# SHARED_HEADER.net
KiCad netlist of a schematic drawn in Altium Designer
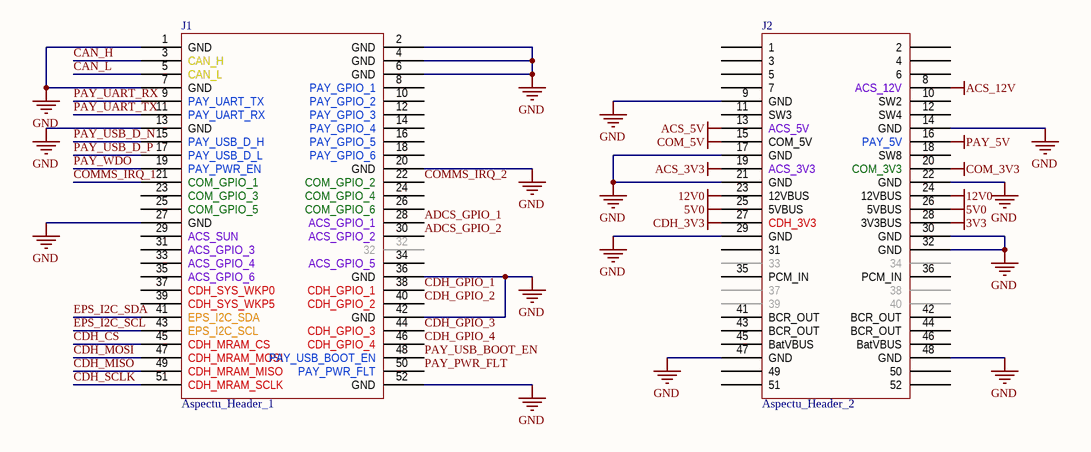
[diagram p0: SHARED_HEADER.SchDoc]

(export (version "E")
  (design (tool "Eeschema 10.0.6"))
  (components
    (comp (ref "J1")
      (value "Aspectu_Header_1")
      (footprint "Aspectu_Header_1")
      (description "Aspectu Header 1")
      (libsource (lib "UBC_Orbit_Shared_Components") (part "Aspectu_Header_1"))
    )
    (comp (ref "J2")
      (value "Aspectu_Header_2")
      (footprint "Aspectu_Header_2")
      (description "Aspectu Header 2")
      (libsource (lib "UBC_Orbit_Shared_Components") (part "Aspectu_Header_2"))
    )
  )
  (nets
    (net (code "1") (name "/ADCS_GPIO_1") (class "Default")
      (node (ref "J1") (pin "28") (pinfunction "ACS_GPIO_1_28") (pintype "passive"))
    )
    (net (code "2") (name "/ADCS_GPIO_2") (class "Default")
      (node (ref "J1") (pin "30") (pinfunction "ACS_GPIO_2_30") (pintype "passive"))
    )
    (net (code "3") (name "/CAN_H") (class "Default")
      (node (ref "J1") (pin "3") (pinfunction "CAN_H_3") (pintype "passive"))
    )
    (net (code "4") (name "/CAN_L") (class "Default")
      (node (ref "J1") (pin "5") (pinfunction "CAN_L_5") (pintype "passive"))
    )
    (net (code "5") (name "/CDH_CS") (class "Default")
      (node (ref "J1") (pin "45") (pinfunction "CDH_MRAM_CS_45") (pintype "passive"))
    )
    (net (code "6") (name "/CDH_GPIO_1") (class "Default")
      (node (ref "J1") (pin "38") (pinfunction "CDH_GPIO_1_38") (pintype "passive"))
    )
    (net (code "7") (name "/CDH_GPIO_2") (class "Default")
      (node (ref "J1") (pin "40") (pinfunction "CDH_GPIO_2_40") (pintype "passive"))
    )
    (net (code "8") (name "/CDH_GPIO_3") (class "Default")
      (node (ref "J1") (pin "44") (pinfunction "CDH_GPIO_3_44") (pintype "passive"))
    )
    (net (code "9") (name "/CDH_GPIO_4") (class "Default")
      (node (ref "J1") (pin "46") (pinfunction "CDH_GPIO_4_46") (pintype "passive"))
    )
    (net (code "10") (name "/CDH_MISO") (class "Default")
      (node (ref "J1") (pin "49") (pinfunction "CDH_MRAM_MISO_49") (pintype "passive"))
    )
    (net (code "11") (name "/CDH_MOSI") (class "Default")
      (node (ref "J1") (pin "47") (pinfunction "CDH_MRAM_MOSI_47") (pintype "passive"))
    )
    (net (code "12") (name "/CDH_SCLK") (class "Default")
      (node (ref "J1") (pin "51") (pinfunction "CDH_MRAM_SCLK_51") (pintype "passive"))
    )
    (net (code "13") (name "/COMMS_IRQ_1") (class "Default")
      (node (ref "J1") (pin "21") (pinfunction "COM_GPIO_1_21") (pintype "passive"))
    )
    (net (code "14") (name "/COMMS_IRQ_2") (class "Default")
      (node (ref "J1") (pin "22") (pinfunction "COM_GPIO_2_22") (pintype "passive"))
    )
    (net (code "15") (name "/EPS_I2C_SCL") (class "Default")
      (node (ref "J1") (pin "43") (pinfunction "EPS_I2C_SCL_43") (pintype "passive"))
    )
    (net (code "16") (name "/EPS_I2C_SDA") (class "Default")
      (node (ref "J1") (pin "41") (pinfunction "EPS_I2C_SDA_41") (pintype "passive"))
    )
    (net (code "17") (name "/PAY_PWR_FLT") (class "Default")
      (node (ref "J1") (pin "50") (pinfunction "PAY_PWR_FLT_50") (pintype "passive"))
    )
    (net (code "18") (name "/PAY_UART_RX") (class "Default")
      (node (ref "J1") (pin "9") (pinfunction "PAY_UART_TX_9") (pintype "passive"))
    )
    (net (code "19") (name "/PAY_UART_TX") (class "Default")
      (node (ref "J1") (pin "11") (pinfunction "PAY_UART_RX_11") (pintype "passive"))
    )
    (net (code "20") (name "/PAY_USB_BOOT_EN") (class "Default")
      (node (ref "J1") (pin "48") (pinfunction "PAY_USB_BOOT_EN_48") (pintype "passive"))
    )
    (net (code "21") (name "/PAY_USB_D_N") (class "Default")
      (node (ref "J1") (pin "15") (pinfunction "PAY_USB_D_H_15") (pintype "passive"))
    )
    (net (code "22") (name "/PAY_USB_D_P") (class "Default")
      (node (ref "J1") (pin "17") (pinfunction "PAY_USB_D_L_17") (pintype "passive"))
    )
    (net (code "23") (name "/PAY_WDO") (class "Default")
      (node (ref "J1") (pin "19") (pinfunction "PAY_PWR_EN_19") (pintype "passive"))
    )
    (net (code "24") (name "3V3") (class "Default")
      (node (ref "J2") (pin "28") (pinfunction "3V3BUS_28") (pintype "power_in"))
    )
    (net (code "25") (name "5V0") (class "Default")
      (node (ref "J2") (pin "25") (pinfunction "5VBUS_25") (pintype "power_in"))
      (node (ref "J2") (pin "26") (pinfunction "5VBUS_26") (pintype "power_in"))
    )
    (net (code "26") (name "12V0") (class "Default")
      (node (ref "J2") (pin "23") (pinfunction "12VBUS_23") (pintype "power_in"))
      (node (ref "J2") (pin "24") (pinfunction "12VBUS_24") (pintype "power_in"))
    )
    (net (code "27") (name "ACS_3V3") (class "Default")
      (node (ref "J2") (pin "19") (pinfunction "ACS_3V3_19") (pintype "passive"))
    )
    (net (code "28") (name "ACS_5V") (class "Default")
      (node (ref "J2") (pin "13") (pinfunction "ACS_5V_13") (pintype "passive"))
    )
    (net (code "29") (name "ACS_12V") (class "Default")
      (node (ref "J2") (pin "8") (pinfunction "ACS_12V_8") (pintype "passive"))
    )
    (net (code "30") (name "CDH_3V3") (class "Default")
      (node (ref "J2") (pin "27") (pinfunction "CDH_3V3_27") (pintype "power_in"))
    )
    (net (code "31") (name "COM_3V3") (class "Default")
      (node (ref "J2") (pin "20") (pinfunction "COM_3V3_20") (pintype "passive"))
    )
    (net (code "32") (name "COM_5V") (class "Default")
      (node (ref "J2") (pin "15") (pinfunction "COM_5V_15") (pintype "passive"))
    )
    (net (code "33") (name "GND") (class "Default")
      (node (ref "J1") (pin "1") (pinfunction "GND_1") (pintype "power_in"))
      (node (ref "J1") (pin "13") (pinfunction "GND_13") (pintype "passive"))
      (node (ref "J1") (pin "2") (pinfunction "GND_2") (pintype "power_in"))
      (node (ref "J1") (pin "20") (pinfunction "GND_20") (pintype "power_in"))
      (node (ref "J1") (pin "27") (pinfunction "GND_27") (pintype "power_in"))
      (node (ref "J1") (pin "36") (pinfunction "GND_36") (pintype "power_in"))
      (node (ref "J1") (pin "4") (pinfunction "GND_4") (pintype "power_in"))
      (node (ref "J1") (pin "42") (pinfunction "GND_42") (pintype "power_in"))
      (node (ref "J1") (pin "52") (pinfunction "GND_52") (pintype "power_in"))
      (node (ref "J1") (pin "6") (pinfunction "GND_6") (pintype "power_in"))
      (node (ref "J1") (pin "7") (pinfunction "GND_7") (pintype "power_in"))
      (node (ref "J2") (pin "14") (pinfunction "GND_14") (pintype "power_in"))
      (node (ref "J2") (pin "17") (pinfunction "GND_17") (pintype "power_in"))
      (node (ref "J2") (pin "21") (pinfunction "GND_21") (pintype "power_in"))
      (node (ref "J2") (pin "22") (pinfunction "GND_22") (pintype "power_in"))
      (node (ref "J2") (pin "29") (pinfunction "GND_29") (pintype "power_in"))
      (node (ref "J2") (pin "30") (pinfunction "GND_30") (pintype "power_in"))
      (node (ref "J2") (pin "32") (pinfunction "GND_32") (pintype "power_in"))
      (node (ref "J2") (pin "47") (pinfunction "GND_47") (pintype "power_in"))
      (node (ref "J2") (pin "48") (pinfunction "GND_48") (pintype "power_in"))
      (node (ref "J2") (pin "9") (pinfunction "GND_9") (pintype "power_in"))
    )
    (net (code "34") (name "PAY_5V") (class "Default")
      (node (ref "J2") (pin "16") (pinfunction "PAY_5V_16") (pintype "passive"))
    )
    (net (code "35") (name "unconnected-(J1-ACS_GPIO_3-Pad31)") (class "Default")
      (node (ref "J1") (pin "31") (pinfunction "ACS_GPIO_3_31") (pintype "passive"))
    )
    (net (code "36") (name "unconnected-(J1-ACS_GPIO_4-Pad33)") (class "Default")
      (node (ref "J1") (pin "33") (pinfunction "ACS_GPIO_4_33") (pintype "passive"))
    )
    (net (code "37") (name "unconnected-(J1-ACS_GPIO_5-Pad34)") (class "Default")
      (node (ref "J1") (pin "34") (pinfunction "ACS_GPIO_5_34") (pintype "passive"))
    )
    (net (code "38") (name "unconnected-(J1-ACS_GPIO_6-Pad35)") (class "Default")
      (node (ref "J1") (pin "35") (pinfunction "ACS_GPIO_6_35") (pintype "passive"))
    )
    (net (code "39") (name "unconnected-(J1-ACS_SUN-Pad29)") (class "Default")
      (node (ref "J1") (pin "29") (pinfunction "ACS_SUN_29") (pintype "passive"))
    )
    (net (code "40") (name "unconnected-(J1-CDH_SYS_WKP0-Pad37)") (class "Default")
      (node (ref "J1") (pin "37") (pinfunction "CDH_SYS_WKP0_37") (pintype "passive"))
    )
    (net (code "41") (name "unconnected-(J1-CDH_SYS_WKP5-Pad39)") (class "Default")
      (node (ref "J1") (pin "39") (pinfunction "CDH_SYS_WKP5_39") (pintype "passive"))
    )
    (net (code "42") (name "unconnected-(J1-COM_GPIO_3-Pad23)") (class "Default")
      (node (ref "J1") (pin "23") (pinfunction "COM_GPIO_3_23") (pintype "passive"))
    )
    (net (code "43") (name "unconnected-(J1-COM_GPIO_4-Pad24)") (class "Default")
      (node (ref "J1") (pin "24") (pinfunction "COM_GPIO_4_24") (pintype "passive"))
    )
    (net (code "44") (name "unconnected-(J1-COM_GPIO_5-Pad25)") (class "Default")
      (node (ref "J1") (pin "25") (pinfunction "COM_GPIO_5_25") (pintype "passive"))
    )
    (net (code "45") (name "unconnected-(J1-COM_GPIO_6-Pad26)") (class "Default")
      (node (ref "J1") (pin "26") (pinfunction "COM_GPIO_6_26") (pintype "passive"))
    )
    (net (code "46") (name "unconnected-(J1-PAY_GPIO_1-Pad8)") (class "Default")
      (node (ref "J1") (pin "8") (pinfunction "PAY_GPIO_1_8") (pintype "passive"))
    )
    (net (code "47") (name "unconnected-(J1-PAY_GPIO_2-Pad10)") (class "Default")
      (node (ref "J1") (pin "10") (pinfunction "PAY_GPIO_2_10") (pintype "passive"))
    )
    (net (code "48") (name "unconnected-(J1-PAY_GPIO_3-Pad12)") (class "Default")
      (node (ref "J1") (pin "12") (pinfunction "PAY_GPIO_3_12") (pintype "passive"))
    )
    (net (code "49") (name "unconnected-(J1-PAY_GPIO_4-Pad14)") (class "Default")
      (node (ref "J1") (pin "14") (pinfunction "PAY_GPIO_4_14") (pintype "passive"))
    )
    (net (code "50") (name "unconnected-(J1-PAY_GPIO_5-Pad16)") (class "Default")
      (node (ref "J1") (pin "16") (pinfunction "PAY_GPIO_5_16") (pintype "passive"))
    )
    (net (code "51") (name "unconnected-(J1-PAY_GPIO_6-Pad18)") (class "Default")
      (node (ref "J1") (pin "18") (pinfunction "PAY_GPIO_6_18") (pintype "passive"))
    )
    (net (code "52") (name "unconnected-(J1-Pad32)") (class "Default")
      (node (ref "J1") (pin "32") (pinfunction "32_32") (pintype "passive"))
    )
    (net (code "53") (name "unconnected-(J2-BCR_OUT-Pad41)") (class "Default")
      (node (ref "J2") (pin "41") (pinfunction "BCR_OUT_41") (pintype "passive"))
    )
    (net (code "54") (name "unconnected-(J2-BCR_OUT-Pad42)") (class "Default")
      (node (ref "J2") (pin "42") (pinfunction "BCR_OUT_42") (pintype "passive"))
    )
    (net (code "55") (name "unconnected-(J2-BCR_OUT-Pad43)") (class "Default")
      (node (ref "J2") (pin "43") (pinfunction "BCR_OUT_43") (pintype "passive"))
    )
    (net (code "56") (name "unconnected-(J2-BCR_OUT-Pad44)") (class "Default")
      (node (ref "J2") (pin "44") (pinfunction "BCR_OUT_44") (pintype "passive"))
    )
    (net (code "57") (name "unconnected-(J2-BatVBUS-Pad45)") (class "Default")
      (node (ref "J2") (pin "45") (pinfunction "BatVBUS_45") (pintype "power_in"))
    )
    (net (code "58") (name "unconnected-(J2-BatVBUS-Pad46)") (class "Default")
      (node (ref "J2") (pin "46") (pinfunction "BatVBUS_46") (pintype "power_in"))
    )
    (net (code "59") (name "unconnected-(J2-PCM_IN-Pad35)") (class "Default")
      (node (ref "J2") (pin "35") (pinfunction "PCM_IN_35") (pintype "passive"))
    )
    (net (code "60") (name "unconnected-(J2-PCM_IN-Pad36)") (class "Default")
      (node (ref "J2") (pin "36") (pinfunction "PCM_IN_36") (pintype "passive"))
    )
    (net (code "61") (name "unconnected-(J2-Pad1)") (class "Default")
      (node (ref "J2") (pin "1") (pinfunction "1_1") (pintype "passive"))
    )
    (net (code "62") (name "unconnected-(J2-Pad2)") (class "Default")
      (node (ref "J2") (pin "2") (pinfunction "2_2") (pintype "passive"))
    )
    (net (code "63") (name "unconnected-(J2-Pad3)") (class "Default")
      (node (ref "J2") (pin "3") (pinfunction "3_3") (pintype "passive"))
    )
    (net (code "64") (name "unconnected-(J2-Pad4)") (class "Default")
      (node (ref "J2") (pin "4") (pinfunction "4_4") (pintype "passive"))
    )
    (net (code "65") (name "unconnected-(J2-Pad5)") (class "Default")
      (node (ref "J2") (pin "5") (pinfunction "5_5") (pintype "passive"))
    )
    (net (code "66") (name "unconnected-(J2-Pad6)") (class "Default")
      (node (ref "J2") (pin "6") (pinfunction "6_6") (pintype "passive"))
    )
    (net (code "67") (name "unconnected-(J2-Pad7)") (class "Default")
      (node (ref "J2") (pin "7") (pinfunction "7_7") (pintype "passive"))
    )
    (net (code "68") (name "unconnected-(J2-Pad31)") (class "Default")
      (node (ref "J2") (pin "31") (pinfunction "31_31") (pintype "passive"))
    )
    (net (code "69") (name "unconnected-(J2-Pad33)") (class "Default")
      (node (ref "J2") (pin "33") (pinfunction "33_33") (pintype "passive"))
    )
    (net (code "70") (name "unconnected-(J2-Pad34)") (class "Default")
      (node (ref "J2") (pin "34") (pinfunction "34_34") (pintype "passive"))
    )
    (net (code "71") (name "unconnected-(J2-Pad37)") (class "Default")
      (node (ref "J2") (pin "37") (pinfunction "37_37") (pintype "passive"))
    )
    (net (code "72") (name "unconnected-(J2-Pad38)") (class "Default")
      (node (ref "J2") (pin "38") (pinfunction "38_38") (pintype "passive"))
    )
    (net (code "73") (name "unconnected-(J2-Pad39)") (class "Default")
      (node (ref "J2") (pin "39") (pinfunction "39_39") (pintype "passive"))
    )
    (net (code "74") (name "unconnected-(J2-Pad40)") (class "Default")
      (node (ref "J2") (pin "40") (pinfunction "40_40") (pintype "passive"))
    )
    (net (code "75") (name "unconnected-(J2-Pad49)") (class "Default")
      (node (ref "J2") (pin "49") (pinfunction "49_49") (pintype "passive"))
    )
    (net (code "76") (name "unconnected-(J2-Pad50)") (class "Default")
      (node (ref "J2") (pin "50") (pinfunction "50_50") (pintype "passive"))
    )
    (net (code "77") (name "unconnected-(J2-Pad51)") (class "Default")
      (node (ref "J2") (pin "51") (pinfunction "51_51") (pintype "passive"))
    )
    (net (code "78") (name "unconnected-(J2-Pad52)") (class "Default")
      (node (ref "J2") (pin "52") (pinfunction "52_52") (pintype "passive"))
    )
    (net (code "79") (name "unconnected-(J2-SW2-Pad10)") (class "Default")
      (node (ref "J2") (pin "10") (pinfunction "SW2_10") (pintype "passive"))
    )
    (net (code "80") (name "unconnected-(J2-SW3-Pad11)") (class "Default")
      (node (ref "J2") (pin "11") (pinfunction "SW3_11") (pintype "passive"))
    )
    (net (code "81") (name "unconnected-(J2-SW4-Pad12)") (class "Default")
      (node (ref "J2") (pin "12") (pinfunction "SW4_12") (pintype "passive"))
    )
    (net (code "82") (name "unconnected-(J2-SW8-Pad18)") (class "Default")
      (node (ref "J2") (pin "18") (pinfunction "SW8_18") (pintype "passive"))
    )
  )
)
